# 11-DPLL-2.net
KiCad netlist of a schematic drawn in Altium Designer
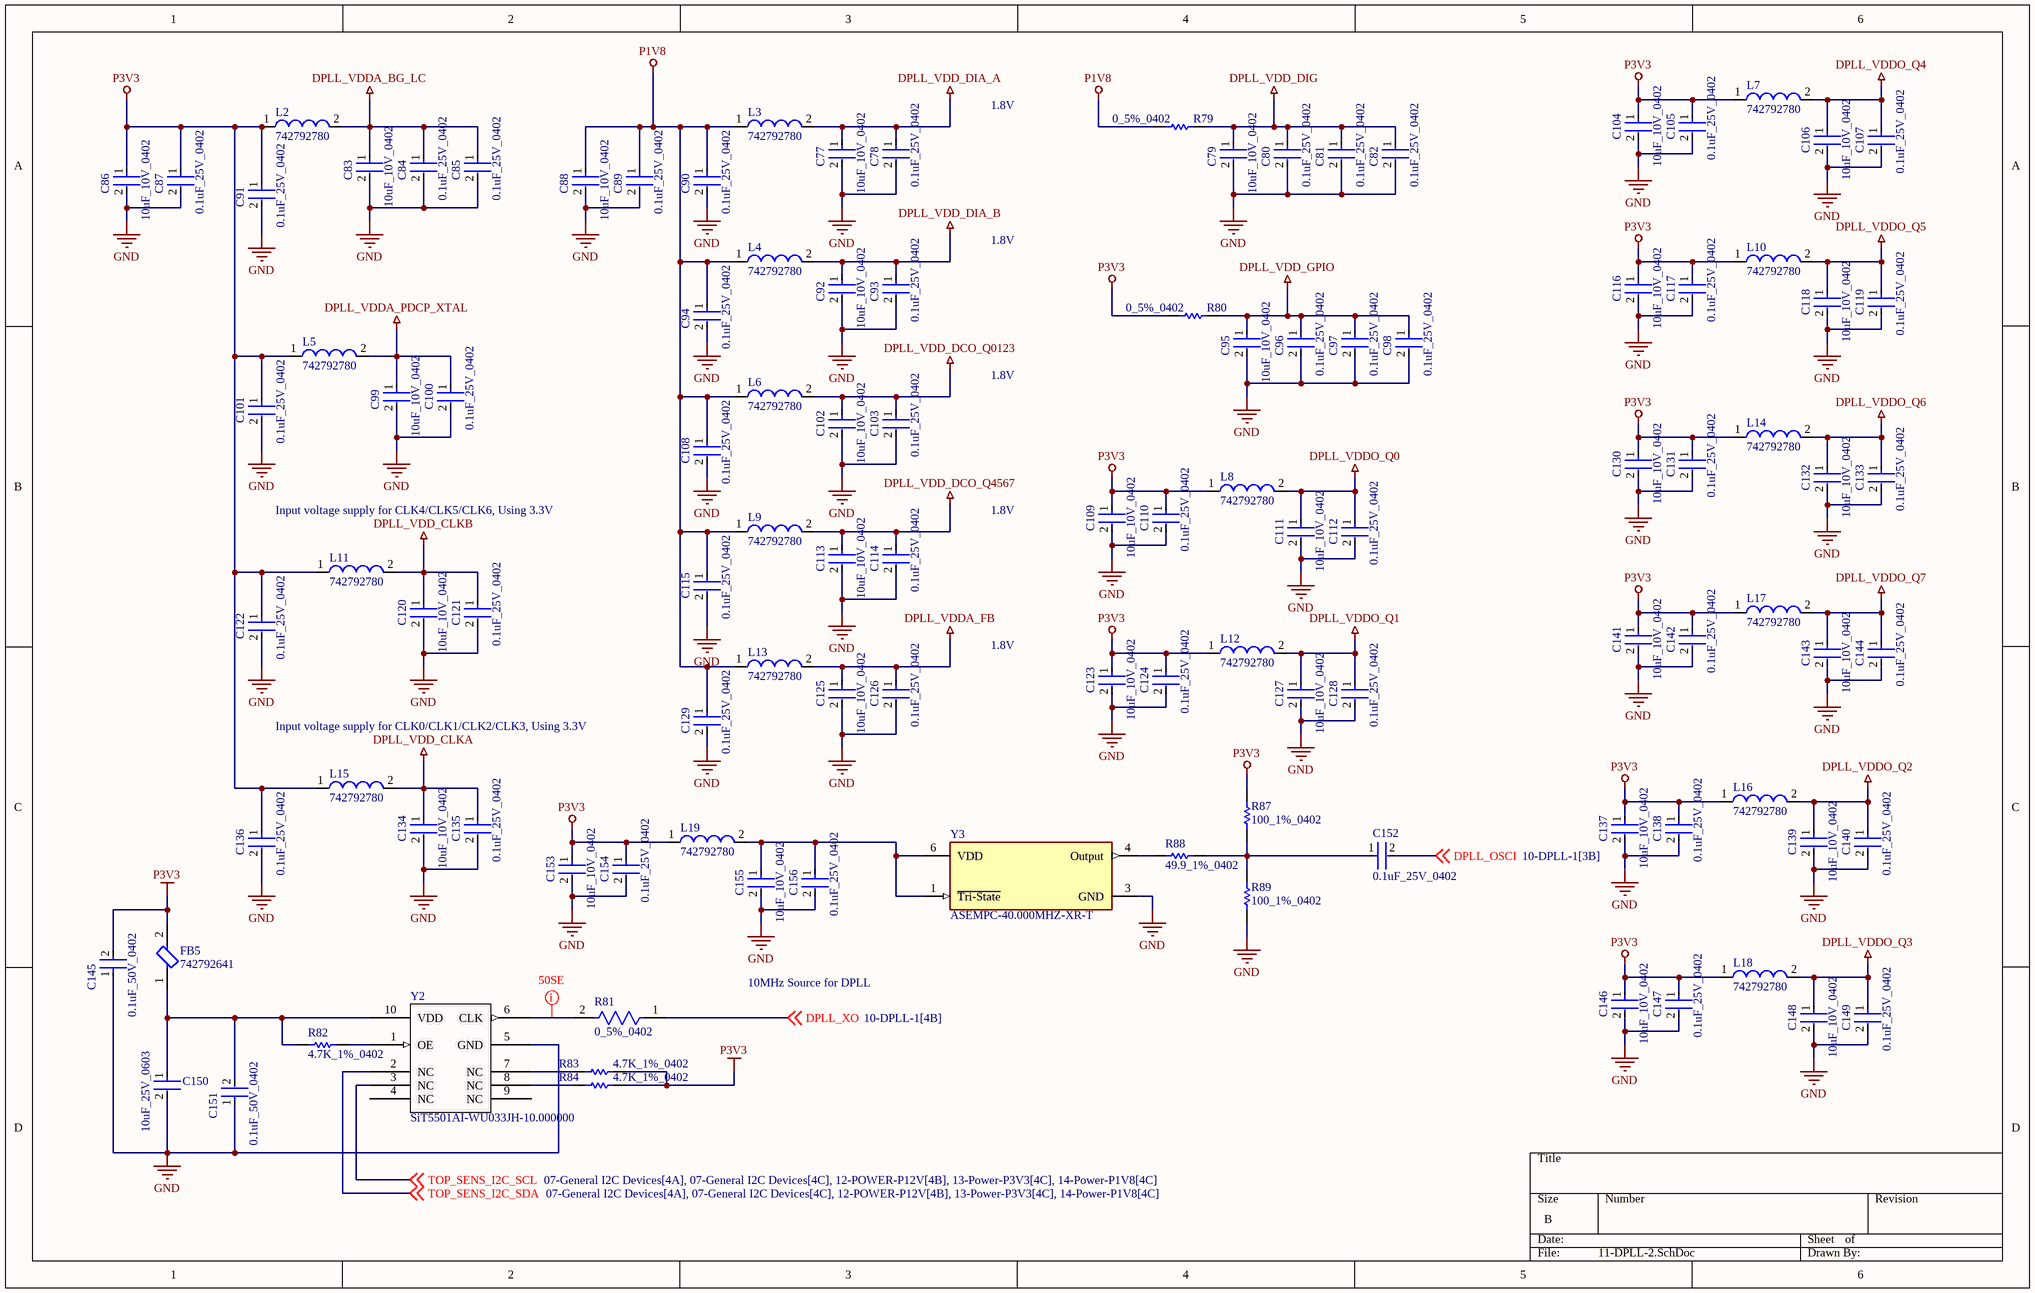
[diagram p0: 11-DPLL-2.SchDoc]

(export (version "E")
  (design (tool "Eeschema 10.0.6"))
  (components
    (comp (ref "C77")
      (value "10uF_10V_0402")
      (footprint "FP-CL05A106MP5NUNC-MFG")
      (description "CAP CER 10UF 10V X5R 0402")
      (fields
        (field (name "OCTOPART") "https://octopart.com/cl05a106mp5nunc-samsung-22457395")
        (field (name "TOLERANCE") "20%")
      )
      (libsource (lib "Altium Content Vault") (part "b4654b650e69147ec39a6b967a45e02"))
    )
    (comp (ref "C78")
      (value "0.1uF_25V_0402")
      (footprint "FP-0402-L_1_0_1-W_0_5_0_1-IPC_C")
      (description "General Purpose Ceramic Capacitor, 0402, 100nF, 10%, X7R, 15%, 25V")
      (fields (field (name "VOLTAGE") "25V") (field (name "TOLERANCE") "10%"))
      (libsource (lib "Altium Content Vault") (part "b4654b650e69147ec39a6b967a45e02"))
    )
    (comp (ref "C79")
      (value "10uF_10V_0402")
      (footprint "FP-CL05A106MP5NUNC-MFG")
      (description "CAP CER 10UF 10V X5R 0402")
      (fields
        (field (name "OCTOPART") "https://octopart.com/cl05a106mp5nunc-samsung-22457395")
        (field (name "TOLERANCE") "20%")
      )
      (libsource (lib "Altium Content Vault") (part "b4654b650e69147ec39a6b967a45e02"))
    )
    (comp (ref "C80")
      (value "0.1uF_25V_0402")
      (footprint "FP-0402-L_1_0_1-W_0_5_0_1-IPC_C")
      (description "General Purpose Ceramic Capacitor, 0402, 100nF, 10%, X7R, 15%, 25V")
      (fields (field (name "VOLTAGE") "25V") (field (name "TOLERANCE") "10%"))
      (libsource (lib "Altium Content Vault") (part "b4654b650e69147ec39a6b967a45e02"))
    )
    (comp (ref "C81")
      (value "0.1uF_25V_0402")
      (footprint "FP-0402-L_1_0_1-W_0_5_0_1-IPC_C")
      (description "General Purpose Ceramic Capacitor, 0402, 100nF, 10%, X7R, 15%, 25V")
      (fields (field (name "VOLTAGE") "25V") (field (name "TOLERANCE") "10%"))
      (libsource (lib "Altium Content Vault") (part "b4654b650e69147ec39a6b967a45e02"))
    )
    (comp (ref "C82")
      (value "0.1uF_25V_0402")
      (footprint "FP-0402-L_1_0_1-W_0_5_0_1-IPC_C")
      (description "General Purpose Ceramic Capacitor, 0402, 100nF, 10%, X7R, 15%, 25V")
      (fields (field (name "VOLTAGE") "25V") (field (name "TOLERANCE") "10%"))
      (libsource (lib "Altium Content Vault") (part "b4654b650e69147ec39a6b967a45e02"))
    )
    (comp (ref "C83")
      (value "10uF_10V_0402")
      (footprint "FP-CL05A106MP5NUNC-MFG")
      (description "CAP CER 10UF 10V X5R 0402")
      (fields
        (field (name "OCTOPART") "https://octopart.com/cl05a106mp5nunc-samsung-22457395")
        (field (name "TOLERANCE") "20%")
      )
      (libsource (lib "Altium Content Vault") (part "b4654b650e69147ec39a6b967a45e02"))
    )
    (comp (ref "C84")
      (value "0.1uF_25V_0402")
      (footprint "FP-0402-L_1_0_1-W_0_5_0_1-IPC_C")
      (description "General Purpose Ceramic Capacitor, 0402, 100nF, 10%, X7R, 15%, 25V")
      (fields (field (name "VOLTAGE") "25V") (field (name "TOLERANCE") "10%"))
      (libsource (lib "Altium Content Vault") (part "b4654b650e69147ec39a6b967a45e02"))
    )
    (comp (ref "C85")
      (value "0.1uF_25V_0402")
      (footprint "FP-0402-L_1_0_1-W_0_5_0_1-IPC_C")
      (description "General Purpose Ceramic Capacitor, 0402, 100nF, 10%, X7R, 15%, 25V")
      (fields (field (name "VOLTAGE") "25V") (field (name "TOLERANCE") "10%"))
      (libsource (lib "Altium Content Vault") (part "b4654b650e69147ec39a6b967a45e02"))
    )
    (comp (ref "C86")
      (value "10uF_10V_0402")
      (footprint "FP-CL05A106MP5NUNC-MFG")
      (description "CAP CER 10UF 10V X5R 0402")
      (fields
        (field (name "OCTOPART") "https://octopart.com/cl05a106mp5nunc-samsung-22457395")
        (field (name "TOLERANCE") "20%")
      )
      (libsource (lib "Altium Content Vault") (part "b4654b650e69147ec39a6b967a45e02"))
    )
    (comp (ref "C87")
      (value "0.1uF_25V_0402")
      (footprint "FP-0402-L_1_0_1-W_0_5_0_1-IPC_C")
      (description "General Purpose Ceramic Capacitor, 0402, 100nF, 10%, X7R, 15%, 25V")
      (fields (field (name "VOLTAGE") "25V") (field (name "TOLERANCE") "10%"))
      (libsource (lib "Altium Content Vault") (part "b4654b650e69147ec39a6b967a45e02"))
    )
    (comp (ref "C88")
      (value "10uF_10V_0402")
      (footprint "FP-CL05A106MP5NUNC-MFG")
      (description "CAP CER 10UF 10V X5R 0402")
      (fields
        (field (name "OCTOPART") "https://octopart.com/cl05a106mp5nunc-samsung-22457395")
        (field (name "TOLERANCE") "20%")
      )
      (libsource (lib "Altium Content Vault") (part "b4654b650e69147ec39a6b967a45e02"))
    )
    (comp (ref "C89")
      (value "0.1uF_25V_0402")
      (footprint "FP-0402-L_1_0_1-W_0_5_0_1-IPC_C")
      (description "General Purpose Ceramic Capacitor, 0402, 100nF, 10%, X7R, 15%, 25V")
      (fields (field (name "VOLTAGE") "25V") (field (name "TOLERANCE") "10%"))
      (libsource (lib "Altium Content Vault") (part "b4654b650e69147ec39a6b967a45e02"))
    )
    (comp (ref "C90")
      (value "0.1uF_25V_0402")
      (footprint "FP-0402-L_1_0_1-W_0_5_0_1-IPC_C")
      (description "General Purpose Ceramic Capacitor, 0402, 100nF, 10%, X7R, 15%, 25V")
      (fields (field (name "VOLTAGE") "25V") (field (name "TOLERANCE") "10%"))
      (libsource (lib "Altium Content Vault") (part "b4654b650e69147ec39a6b967a45e02"))
    )
    (comp (ref "C91")
      (value "0.1uF_25V_0402")
      (footprint "FP-0402-L_1_0_1-W_0_5_0_1-IPC_C")
      (description "General Purpose Ceramic Capacitor, 0402, 100nF, 10%, X7R, 15%, 25V")
      (fields (field (name "VOLTAGE") "25V") (field (name "TOLERANCE") "10%"))
      (libsource (lib "Altium Content Vault") (part "b4654b650e69147ec39a6b967a45e02"))
    )
    (comp (ref "C92")
      (value "10uF_10V_0402")
      (footprint "FP-CL05A106MP5NUNC-MFG")
      (description "CAP CER 10UF 10V X5R 0402")
      (fields
        (field (name "OCTOPART") "https://octopart.com/cl05a106mp5nunc-samsung-22457395")
        (field (name "TOLERANCE") "20%")
      )
      (libsource (lib "Altium Content Vault") (part "b4654b650e69147ec39a6b967a45e02"))
    )
    (comp (ref "C93")
      (value "0.1uF_25V_0402")
      (footprint "FP-0402-L_1_0_1-W_0_5_0_1-IPC_C")
      (description "General Purpose Ceramic Capacitor, 0402, 100nF, 10%, X7R, 15%, 25V")
      (fields (field (name "VOLTAGE") "25V") (field (name "TOLERANCE") "10%"))
      (libsource (lib "Altium Content Vault") (part "b4654b650e69147ec39a6b967a45e02"))
    )
    (comp (ref "C94")
      (value "0.1uF_25V_0402")
      (footprint "FP-0402-L_1_0_1-W_0_5_0_1-IPC_C")
      (description "General Purpose Ceramic Capacitor, 0402, 100nF, 10%, X7R, 15%, 25V")
      (fields (field (name "VOLTAGE") "25V") (field (name "TOLERANCE") "10%"))
      (libsource (lib "Altium Content Vault") (part "b4654b650e69147ec39a6b967a45e02"))
    )
    (comp (ref "C95")
      (value "10uF_10V_0402")
      (footprint "FP-CL05A106MP5NUNC-MFG")
      (description "CAP CER 10UF 10V X5R 0402")
      (fields
        (field (name "OCTOPART") "https://octopart.com/cl05a106mp5nunc-samsung-22457395")
        (field (name "TOLERANCE") "20%")
      )
      (libsource (lib "Altium Content Vault") (part "b4654b650e69147ec39a6b967a45e02"))
    )
    (comp (ref "C96")
      (value "0.1uF_25V_0402")
      (footprint "FP-0402-L_1_0_1-W_0_5_0_1-IPC_C")
      (description "General Purpose Ceramic Capacitor, 0402, 100nF, 10%, X7R, 15%, 25V")
      (fields (field (name "VOLTAGE") "25V") (field (name "TOLERANCE") "10%"))
      (libsource (lib "Altium Content Vault") (part "b4654b650e69147ec39a6b967a45e02"))
    )
    (comp (ref "C97")
      (value "0.1uF_25V_0402")
      (footprint "FP-0402-L_1_0_1-W_0_5_0_1-IPC_C")
      (description "General Purpose Ceramic Capacitor, 0402, 100nF, 10%, X7R, 15%, 25V")
      (fields (field (name "VOLTAGE") "25V") (field (name "TOLERANCE") "10%"))
      (libsource (lib "Altium Content Vault") (part "b4654b650e69147ec39a6b967a45e02"))
    )
    (comp (ref "C98")
      (value "0.1uF_25V_0402")
      (footprint "FP-0402-L_1_0_1-W_0_5_0_1-IPC_C")
      (description "General Purpose Ceramic Capacitor, 0402, 100nF, 10%, X7R, 15%, 25V")
      (fields (field (name "VOLTAGE") "25V") (field (name "TOLERANCE") "10%"))
      (libsource (lib "Altium Content Vault") (part "b4654b650e69147ec39a6b967a45e02"))
    )
    (comp (ref "C99")
      (value "10uF_10V_0402")
      (footprint "FP-CL05A106MP5NUNC-MFG")
      (description "CAP CER 10UF 10V X5R 0402")
      (fields
        (field (name "OCTOPART") "https://octopart.com/cl05a106mp5nunc-samsung-22457395")
        (field (name "TOLERANCE") "20%")
      )
      (libsource (lib "Altium Content Vault") (part "b4654b650e69147ec39a6b967a45e02"))
    )
    (comp (ref "C100")
      (value "0.1uF_25V_0402")
      (footprint "FP-0402-L_1_0_1-W_0_5_0_1-IPC_C")
      (description "General Purpose Ceramic Capacitor, 0402, 100nF, 10%, X7R, 15%, 25V")
      (fields (field (name "VOLTAGE") "25V") (field (name "TOLERANCE") "10%"))
      (libsource (lib "Altium Content Vault") (part "b4654b650e69147ec39a6b967a45e02"))
    )
    (comp (ref "C101")
      (value "0.1uF_25V_0402")
      (footprint "FP-0402-L_1_0_1-W_0_5_0_1-IPC_C")
      (description "General Purpose Ceramic Capacitor, 0402, 100nF, 10%, X7R, 15%, 25V")
      (fields (field (name "VOLTAGE") "25V") (field (name "TOLERANCE") "10%"))
      (libsource (lib "Altium Content Vault") (part "b4654b650e69147ec39a6b967a45e02"))
    )
    (comp (ref "C102")
      (value "10uF_10V_0402")
      (footprint "FP-CL05A106MP5NUNC-MFG")
      (description "CAP CER 10UF 10V X5R 0402")
      (fields
        (field (name "OCTOPART") "https://octopart.com/cl05a106mp5nunc-samsung-22457395")
        (field (name "TOLERANCE") "20%")
      )
      (libsource (lib "Altium Content Vault") (part "b4654b650e69147ec39a6b967a45e02"))
    )
    (comp (ref "C103")
      (value "0.1uF_25V_0402")
      (footprint "FP-0402-L_1_0_1-W_0_5_0_1-IPC_C")
      (description "General Purpose Ceramic Capacitor, 0402, 100nF, 10%, X7R, 15%, 25V")
      (fields (field (name "VOLTAGE") "25V") (field (name "TOLERANCE") "10%"))
      (libsource (lib "Altium Content Vault") (part "b4654b650e69147ec39a6b967a45e02"))
    )
    (comp (ref "C104")
      (value "10uF_10V_0402")
      (footprint "FP-CL05A106MP5NUNC-MFG")
      (description "CAP CER 10UF 10V X5R 0402")
      (fields
        (field (name "OCTOPART") "https://octopart.com/cl05a106mp5nunc-samsung-22457395")
        (field (name "TOLERANCE") "20%")
      )
      (libsource (lib "Altium Content Vault") (part "b4654b650e69147ec39a6b967a45e02"))
    )
    (comp (ref "C105")
      (value "0.1uF_25V_0402")
      (footprint "FP-0402-L_1_0_1-W_0_5_0_1-IPC_C")
      (description "General Purpose Ceramic Capacitor, 0402, 100nF, 10%, X7R, 15%, 25V")
      (fields (field (name "VOLTAGE") "25V") (field (name "TOLERANCE") "10%"))
      (libsource (lib "Altium Content Vault") (part "b4654b650e69147ec39a6b967a45e02"))
    )
    (comp (ref "C106")
      (value "10uF_10V_0402")
      (footprint "FP-CL05A106MP5NUNC-MFG")
      (description "CAP CER 10UF 10V X5R 0402")
      (fields
        (field (name "OCTOPART") "https://octopart.com/cl05a106mp5nunc-samsung-22457395")
        (field (name "TOLERANCE") "20%")
      )
      (libsource (lib "Altium Content Vault") (part "b4654b650e69147ec39a6b967a45e02"))
    )
    (comp (ref "C107")
      (value "0.1uF_25V_0402")
      (footprint "FP-0402-L_1_0_1-W_0_5_0_1-IPC_C")
      (description "General Purpose Ceramic Capacitor, 0402, 100nF, 10%, X7R, 15%, 25V")
      (fields (field (name "VOLTAGE") "25V") (field (name "TOLERANCE") "10%"))
      (libsource (lib "Altium Content Vault") (part "b4654b650e69147ec39a6b967a45e02"))
    )
    (comp (ref "C108")
      (value "0.1uF_25V_0402")
      (footprint "FP-0402-L_1_0_1-W_0_5_0_1-IPC_C")
      (description "General Purpose Ceramic Capacitor, 0402, 100nF, 10%, X7R, 15%, 25V")
      (fields (field (name "VOLTAGE") "25V") (field (name "TOLERANCE") "10%"))
      (libsource (lib "Altium Content Vault") (part "b4654b650e69147ec39a6b967a45e02"))
    )
    (comp (ref "C109")
      (value "10uF_10V_0402")
      (footprint "FP-CL05A106MP5NUNC-MFG")
      (description "CAP CER 10UF 10V X5R 0402")
      (fields
        (field (name "OCTOPART") "https://octopart.com/cl05a106mp5nunc-samsung-22457395")
        (field (name "TOLERANCE") "20%")
      )
      (libsource (lib "Altium Content Vault") (part "b4654b650e69147ec39a6b967a45e02"))
    )
    (comp (ref "C110")
      (value "0.1uF_25V_0402")
      (footprint "FP-0402-L_1_0_1-W_0_5_0_1-IPC_C")
      (description "General Purpose Ceramic Capacitor, 0402, 100nF, 10%, X7R, 15%, 25V")
      (fields (field (name "VOLTAGE") "25V") (field (name "TOLERANCE") "10%"))
      (libsource (lib "Altium Content Vault") (part "b4654b650e69147ec39a6b967a45e02"))
    )
    (comp (ref "C111")
      (value "10uF_10V_0402")
      (footprint "FP-CL05A106MP5NUNC-MFG")
      (description "CAP CER 10UF 10V X5R 0402")
      (fields
        (field (name "OCTOPART") "https://octopart.com/cl05a106mp5nunc-samsung-22457395")
        (field (name "TOLERANCE") "20%")
      )
      (libsource (lib "Altium Content Vault") (part "b4654b650e69147ec39a6b967a45e02"))
    )
    (comp (ref "C112")
      (value "0.1uF_25V_0402")
      (footprint "FP-0402-L_1_0_1-W_0_5_0_1-IPC_C")
      (description "General Purpose Ceramic Capacitor, 0402, 100nF, 10%, X7R, 15%, 25V")
      (fields (field (name "VOLTAGE") "25V") (field (name "TOLERANCE") "10%"))
      (libsource (lib "Altium Content Vault") (part "b4654b650e69147ec39a6b967a45e02"))
    )
    (comp (ref "C113")
      (value "10uF_10V_0402")
      (footprint "FP-CL05A106MP5NUNC-MFG")
      (description "CAP CER 10UF 10V X5R 0402")
      (fields
        (field (name "OCTOPART") "https://octopart.com/cl05a106mp5nunc-samsung-22457395")
        (field (name "TOLERANCE") "20%")
      )
      (libsource (lib "Altium Content Vault") (part "b4654b650e69147ec39a6b967a45e02"))
    )
    (comp (ref "C114")
      (value "0.1uF_25V_0402")
      (footprint "FP-0402-L_1_0_1-W_0_5_0_1-IPC_C")
      (description "General Purpose Ceramic Capacitor, 0402, 100nF, 10%, X7R, 15%, 25V")
      (fields (field (name "VOLTAGE") "25V") (field (name "TOLERANCE") "10%"))
      (libsource (lib "Altium Content Vault") (part "b4654b650e69147ec39a6b967a45e02"))
    )
    (comp (ref "C115")
      (value "0.1uF_25V_0402")
      (footprint "FP-0402-L_1_0_1-W_0_5_0_1-IPC_C")
      (description "General Purpose Ceramic Capacitor, 0402, 100nF, 10%, X7R, 15%, 25V")
      (fields (field (name "VOLTAGE") "25V") (field (name "TOLERANCE") "10%"))
      (libsource (lib "Altium Content Vault") (part "b4654b650e69147ec39a6b967a45e02"))
    )
    (comp (ref "C116")
      (value "10uF_10V_0402")
      (footprint "FP-CL05A106MP5NUNC-MFG")
      (description "CAP CER 10UF 10V X5R 0402")
      (fields
        (field (name "OCTOPART") "https://octopart.com/cl05a106mp5nunc-samsung-22457395")
        (field (name "TOLERANCE") "20%")
      )
      (libsource (lib "Altium Content Vault") (part "b4654b650e69147ec39a6b967a45e02"))
    )
    (comp (ref "C117")
      (value "0.1uF_25V_0402")
      (footprint "FP-0402-L_1_0_1-W_0_5_0_1-IPC_C")
      (description "General Purpose Ceramic Capacitor, 0402, 100nF, 10%, X7R, 15%, 25V")
      (fields (field (name "VOLTAGE") "25V") (field (name "TOLERANCE") "10%"))
      (libsource (lib "Altium Content Vault") (part "b4654b650e69147ec39a6b967a45e02"))
    )
    (comp (ref "C118")
      (value "10uF_10V_0402")
      (footprint "FP-CL05A106MP5NUNC-MFG")
      (description "CAP CER 10UF 10V X5R 0402")
      (fields
        (field (name "OCTOPART") "https://octopart.com/cl05a106mp5nunc-samsung-22457395")
        (field (name "TOLERANCE") "20%")
      )
      (libsource (lib "Altium Content Vault") (part "b4654b650e69147ec39a6b967a45e02"))
    )
    (comp (ref "C119")
      (value "0.1uF_25V_0402")
      (footprint "FP-0402-L_1_0_1-W_0_5_0_1-IPC_C")
      (description "General Purpose Ceramic Capacitor, 0402, 100nF, 10%, X7R, 15%, 25V")
      (fields (field (name "VOLTAGE") "25V") (field (name "TOLERANCE") "10%"))
      (libsource (lib "Altium Content Vault") (part "b4654b650e69147ec39a6b967a45e02"))
    )
    (comp (ref "C120")
      (value "10uF_10V_0402")
      (footprint "FP-CL05A106MP5NUNC-MFG")
      (description "CAP CER 10UF 10V X5R 0402")
      (fields
        (field (name "OCTOPART") "https://octopart.com/cl05a106mp5nunc-samsung-22457395")
        (field (name "TOLERANCE") "20%")
      )
      (libsource (lib "Altium Content Vault") (part "b4654b650e69147ec39a6b967a45e02"))
    )
    (comp (ref "C121")
      (value "0.1uF_25V_0402")
      (footprint "FP-0402-L_1_0_1-W_0_5_0_1-IPC_C")
      (description "General Purpose Ceramic Capacitor, 0402, 100nF, 10%, X7R, 15%, 25V")
      (fields (field (name "VOLTAGE") "25V") (field (name "TOLERANCE") "10%"))
      (libsource (lib "Altium Content Vault") (part "b4654b650e69147ec39a6b967a45e02"))
    )
    (comp (ref "C122")
      (value "0.1uF_25V_0402")
      (footprint "FP-0402-L_1_0_1-W_0_5_0_1-IPC_C")
      (description "General Purpose Ceramic Capacitor, 0402, 100nF, 10%, X7R, 15%, 25V")
      (fields (field (name "VOLTAGE") "25V") (field (name "TOLERANCE") "10%"))
      (libsource (lib "Altium Content Vault") (part "b4654b650e69147ec39a6b967a45e02"))
    )
    (comp (ref "C123")
      (value "10uF_10V_0402")
      (footprint "FP-CL05A106MP5NUNC-MFG")
      (description "CAP CER 10UF 10V X5R 0402")
      (fields
        (field (name "OCTOPART") "https://octopart.com/cl05a106mp5nunc-samsung-22457395")
        (field (name "TOLERANCE") "20%")
      )
      (libsource (lib "Altium Content Vault") (part "b4654b650e69147ec39a6b967a45e02"))
    )
    (comp (ref "C124")
      (value "0.1uF_25V_0402")
      (footprint "FP-0402-L_1_0_1-W_0_5_0_1-IPC_C")
      (description "General Purpose Ceramic Capacitor, 0402, 100nF, 10%, X7R, 15%, 25V")
      (fields (field (name "VOLTAGE") "25V") (field (name "TOLERANCE") "10%"))
      (libsource (lib "Altium Content Vault") (part "b4654b650e69147ec39a6b967a45e02"))
    )
    (comp (ref "C125")
      (value "10uF_10V_0402")
      (footprint "FP-CL05A106MP5NUNC-MFG")
      (description "CAP CER 10UF 10V X5R 0402")
      (fields
        (field (name "OCTOPART") "https://octopart.com/cl05a106mp5nunc-samsung-22457395")
        (field (name "TOLERANCE") "20%")
      )
      (libsource (lib "Altium Content Vault") (part "b4654b650e69147ec39a6b967a45e02"))
    )
    (comp (ref "C126")
      (value "0.1uF_25V_0402")
      (footprint "FP-0402-L_1_0_1-W_0_5_0_1-IPC_C")
      (description "General Purpose Ceramic Capacitor, 0402, 100nF, 10%, X7R, 15%, 25V")
      (fields (field (name "VOLTAGE") "25V") (field (name "TOLERANCE") "10%"))
      (libsource (lib "Altium Content Vault") (part "b4654b650e69147ec39a6b967a45e02"))
    )
    (comp (ref "C127")
      (value "10uF_10V_0402")
      (footprint "FP-CL05A106MP5NUNC-MFG")
      (description "CAP CER 10UF 10V X5R 0402")
      (fields
        (field (name "OCTOPART") "https://octopart.com/cl05a106mp5nunc-samsung-22457395")
        (field (name "TOLERANCE") "20%")
      )
      (libsource (lib "Altium Content Vault") (part "b4654b650e69147ec39a6b967a45e02"))
    )
    (comp (ref "C128")
      (value "0.1uF_25V_0402")
      (footprint "FP-0402-L_1_0_1-W_0_5_0_1-IPC_C")
      (description "General Purpose Ceramic Capacitor, 0402, 100nF, 10%, X7R, 15%, 25V")
      (fields (field (name "VOLTAGE") "25V") (field (name "TOLERANCE") "10%"))
      (libsource (lib "Altium Content Vault") (part "b4654b650e69147ec39a6b967a45e02"))
    )
    (comp (ref "C129")
      (value "0.1uF_25V_0402")
      (footprint "FP-0402-L_1_0_1-W_0_5_0_1-IPC_C")
      (description "General Purpose Ceramic Capacitor, 0402, 100nF, 10%, X7R, 15%, 25V")
      (fields (field (name "VOLTAGE") "25V") (field (name "TOLERANCE") "10%"))
      (libsource (lib "Altium Content Vault") (part "b4654b650e69147ec39a6b967a45e02"))
    )
    (comp (ref "C130")
      (value "10uF_10V_0402")
      (footprint "FP-CL05A106MP5NUNC-MFG")
      (description "CAP CER 10UF 10V X5R 0402")
      (fields
        (field (name "OCTOPART") "https://octopart.com/cl05a106mp5nunc-samsung-22457395")
        (field (name "TOLERANCE") "20%")
      )
      (libsource (lib "Altium Content Vault") (part "b4654b650e69147ec39a6b967a45e02"))
    )
    (comp (ref "C131")
      (value "0.1uF_25V_0402")
      (footprint "FP-0402-L_1_0_1-W_0_5_0_1-IPC_C")
      (description "General Purpose Ceramic Capacitor, 0402, 100nF, 10%, X7R, 15%, 25V")
      (fields (field (name "VOLTAGE") "25V") (field (name "TOLERANCE") "10%"))
      (libsource (lib "Altium Content Vault") (part "b4654b650e69147ec39a6b967a45e02"))
    )
    (comp (ref "C132")
      (value "10uF_10V_0402")
      (footprint "FP-CL05A106MP5NUNC-MFG")
      (description "CAP CER 10UF 10V X5R 0402")
      (fields
        (field (name "OCTOPART") "https://octopart.com/cl05a106mp5nunc-samsung-22457395")
        (field (name "TOLERANCE") "20%")
      )
      (libsource (lib "Altium Content Vault") (part "b4654b650e69147ec39a6b967a45e02"))
    )
    (comp (ref "C133")
      (value "0.1uF_25V_0402")
      (footprint "FP-0402-L_1_0_1-W_0_5_0_1-IPC_C")
      (description "General Purpose Ceramic Capacitor, 0402, 100nF, 10%, X7R, 15%, 25V")
      (fields (field (name "VOLTAGE") "25V") (field (name "TOLERANCE") "10%"))
      (libsource (lib "Altium Content Vault") (part "b4654b650e69147ec39a6b967a45e02"))
    )
    (comp (ref "C134")
      (value "10uF_10V_0402")
      (footprint "FP-CL05A106MP5NUNC-MFG")
      (description "CAP CER 10UF 10V X5R 0402")
      (fields
        (field (name "OCTOPART") "https://octopart.com/cl05a106mp5nunc-samsung-22457395")
        (field (name "TOLERANCE") "20%")
      )
      (libsource (lib "Altium Content Vault") (part "b4654b650e69147ec39a6b967a45e02"))
    )
    (comp (ref "C135")
      (value "0.1uF_25V_0402")
      (footprint "FP-0402-L_1_0_1-W_0_5_0_1-IPC_C")
      (description "General Purpose Ceramic Capacitor, 0402, 100nF, 10%, X7R, 15%, 25V")
      (fields (field (name "VOLTAGE") "25V") (field (name "TOLERANCE") "10%"))
      (libsource (lib "Altium Content Vault") (part "b4654b650e69147ec39a6b967a45e02"))
    )
    (comp (ref "C136")
      (value "0.1uF_25V_0402")
      (footprint "FP-0402-L_1_0_1-W_0_5_0_1-IPC_C")
      (description "General Purpose Ceramic Capacitor, 0402, 100nF, 10%, X7R, 15%, 25V")
      (fields (field (name "VOLTAGE") "25V") (field (name "TOLERANCE") "10%"))
      (libsource (lib "Altium Content Vault") (part "b4654b650e69147ec39a6b967a45e02"))
    )
    (comp (ref "C137")
      (value "10uF_10V_0402")
      (footprint "FP-CL05A106MP5NUNC-MFG")
      (description "CAP CER 10UF 10V X5R 0402")
      (fields
        (field (name "OCTOPART") "https://octopart.com/cl05a106mp5nunc-samsung-22457395")
        (field (name "TOLERANCE") "20%")
      )
      (libsource (lib "Altium Content Vault") (part "b4654b650e69147ec39a6b967a45e02"))
    )
    (comp (ref "C138")
      (value "0.1uF_25V_0402")
      (footprint "FP-0402-L_1_0_1-W_0_5_0_1-IPC_C")
      (description "General Purpose Ceramic Capacitor, 0402, 100nF, 10%, X7R, 15%, 25V")
      (fields (field (name "VOLTAGE") "25V") (field (name "TOLERANCE") "10%"))
      (libsource (lib "Altium Content Vault") (part "b4654b650e69147ec39a6b967a45e02"))
    )
    (comp (ref "C139")
      (value "10uF_10V_0402")
      (footprint "FP-CL05A106MP5NUNC-MFG")
      (description "CAP CER 10UF 10V X5R 0402")
      (fields
        (field (name "OCTOPART") "https://octopart.com/cl05a106mp5nunc-samsung-22457395")
        (field (name "TOLERANCE") "20%")
      )
      (libsource (lib "Altium Content Vault") (part "b4654b650e69147ec39a6b967a45e02"))
    )
    (comp (ref "C140")
      (value "0.1uF_25V_0402")
      (footprint "FP-0402-L_1_0_1-W_0_5_0_1-IPC_C")
      (description "General Purpose Ceramic Capacitor, 0402, 100nF, 10%, X7R, 15%, 25V")
      (fields (field (name "VOLTAGE") "25V") (field (name "TOLERANCE") "10%"))
      (libsource (lib "Altium Content Vault") (part "b4654b650e69147ec39a6b967a45e02"))
    )
    (comp (ref "C141")
      (value "10uF_10V_0402")
      (footprint "FP-CL05A106MP5NUNC-MFG")
      (description "CAP CER 10UF 10V X5R 0402")
      (fields
        (field (name "OCTOPART") "https://octopart.com/cl05a106mp5nunc-samsung-22457395")
        (field (name "TOLERANCE") "20%")
      )
      (libsource (lib "Altium Content Vault") (part "b4654b650e69147ec39a6b967a45e02"))
    )
    (comp (ref "C142")
      (value "0.1uF_25V_0402")
      (footprint "FP-0402-L_1_0_1-W_0_5_0_1-IPC_C")
      (description "General Purpose Ceramic Capacitor, 0402, 100nF, 10%, X7R, 15%, 25V")
      (fields (field (name "VOLTAGE") "25V") (field (name "TOLERANCE") "10%"))
      (libsource (lib "Altium Content Vault") (part "b4654b650e69147ec39a6b967a45e02"))
    )
    (comp (ref "C143")
      (value "10uF_10V_0402")
      (footprint "FP-CL05A106MP5NUNC-MFG")
      (description "CAP CER 10UF 10V X5R 0402")
      (fields
        (field (name "OCTOPART") "https://octopart.com/cl05a106mp5nunc-samsung-22457395")
        (field (name "TOLERANCE") "20%")
      )
      (libsource (lib "Altium Content Vault") (part "b4654b650e69147ec39a6b967a45e02"))
    )
    (comp (ref "C144")
      (value "0.1uF_25V_0402")
      (footprint "FP-0402-L_1_0_1-W_0_5_0_1-IPC_C")
      (description "General Purpose Ceramic Capacitor, 0402, 100nF, 10%, X7R, 15%, 25V")
      (fields (field (name "VOLTAGE") "25V") (field (name "TOLERANCE") "10%"))
      (libsource (lib "Altium Content Vault") (part "b4654b650e69147ec39a6b967a45e02"))
    )
    (comp (ref "C145")
      (value "0.1uF_50V_0402")
      (footprint "FP-C1005-050-0_05-IPC_C")
      (description "Multilayer Ceramic Capacitors 100nF ±10% 50V X7R SMD 0402")
      (fields (field (name "VOLTAGE") "50V") (field (name "TOLERANCE") "10%"))
      (libsource (lib "Altium Content Vault") (part "b4654b650e69147ec39a6b967a45e02"))
    )
    (comp (ref "C146")
      (value "10uF_10V_0402")
      (footprint "FP-CL05A106MP5NUNC-MFG")
      (description "CAP CER 10UF 10V X5R 0402")
      (fields
        (field (name "OCTOPART") "https://octopart.com/cl05a106mp5nunc-samsung-22457395")
        (field (name "TOLERANCE") "20%")
      )
      (libsource (lib "Altium Content Vault") (part "b4654b650e69147ec39a6b967a45e02"))
    )
    (comp (ref "C147")
      (value "0.1uF_25V_0402")
      (footprint "FP-0402-L_1_0_1-W_0_5_0_1-IPC_C")
      (description "General Purpose Ceramic Capacitor, 0402, 100nF, 10%, X7R, 15%, 25V")
      (fields (field (name "VOLTAGE") "25V") (field (name "TOLERANCE") "10%"))
      (libsource (lib "Altium Content Vault") (part "b4654b650e69147ec39a6b967a45e02"))
    )
    (comp (ref "C148")
      (value "10uF_10V_0402")
      (footprint "FP-CL05A106MP5NUNC-MFG")
      (description "CAP CER 10UF 10V X5R 0402")
      (fields
        (field (name "OCTOPART") "https://octopart.com/cl05a106mp5nunc-samsung-22457395")
        (field (name "TOLERANCE") "20%")
      )
      (libsource (lib "Altium Content Vault") (part "b4654b650e69147ec39a6b967a45e02"))
    )
    (comp (ref "C149")
      (value "0.1uF_25V_0402")
      (footprint "FP-0402-L_1_0_1-W_0_5_0_1-IPC_C")
      (description "General Purpose Ceramic Capacitor, 0402, 100nF, 10%, X7R, 15%, 25V")
      (fields (field (name "VOLTAGE") "25V") (field (name "TOLERANCE") "10%"))
      (libsource (lib "Altium Content Vault") (part "b4654b650e69147ec39a6b967a45e02"))
    )
    (comp (ref "C150")
      (value "10uF_25V_0603")
      (footprint "FP-CL10-IPC_C")
      (description "Cap Ceramic 10uF 25V X5R ±20% Pad SMD 0603 +85°C T/R")
      (fields (field (name "TOLERANCE") "20%"))
      (libsource (lib "Altium Content Vault") (part "b4654b650e69147ec39a6b967a45e02"))
    )
    (comp (ref "C151")
      (value "0.1uF_50V_0402")
      (footprint "FP-C1005-050-0_05-IPC_C")
      (description "Multilayer Ceramic Capacitors 100nF ±10% 50V X7R SMD 0402")
      (fields (field (name "VOLTAGE") "50V") (field (name "TOLERANCE") "10%"))
      (libsource (lib "Altium Content Vault") (part "b4654b650e69147ec39a6b967a45e02"))
    )
    (comp (ref "C152")
      (value "0.1uF_25V_0402")
      (footprint "FP-0402-L_1_0_1-W_0_5_0_1-IPC_C")
      (description "General Purpose Ceramic Capacitor, 0402, 100nF, 10%, X7R, 15%, 25V")
      (fields (field (name "VOLTAGE") "25V") (field (name "TOLERANCE") "10%"))
      (libsource (lib "Altium Content Vault") (part "b4654b650e69147ec39a6b967a45e02"))
    )
    (comp (ref "C153")
      (value "10uF_10V_0402")
      (footprint "FP-CL05A106MP5NUNC-MFG")
      (description "CAP CER 10UF 10V X5R 0402")
      (fields
        (field (name "OCTOPART") "https://octopart.com/cl05a106mp5nunc-samsung-22457395")
        (field (name "TOLERANCE") "20%")
      )
      (libsource (lib "Altium Content Vault") (part "b4654b650e69147ec39a6b967a45e02"))
    )
    (comp (ref "C154")
      (value "0.1uF_25V_0402")
      (footprint "FP-0402-L_1_0_1-W_0_5_0_1-IPC_C")
      (description "General Purpose Ceramic Capacitor, 0402, 100nF, 10%, X7R, 15%, 25V")
      (fields (field (name "VOLTAGE") "25V") (field (name "TOLERANCE") "10%"))
      (libsource (lib "Altium Content Vault") (part "b4654b650e69147ec39a6b967a45e02"))
    )
    (comp (ref "C155")
      (value "10uF_10V_0402")
      (footprint "FP-CL05A106MP5NUNC-MFG")
      (description "CAP CER 10UF 10V X5R 0402")
      (fields
        (field (name "OCTOPART") "https://octopart.com/cl05a106mp5nunc-samsung-22457395")
        (field (name "TOLERANCE") "20%")
      )
      (libsource (lib "Altium Content Vault") (part "b4654b650e69147ec39a6b967a45e02"))
    )
    (comp (ref "C156")
      (value "0.1uF_25V_0402")
      (footprint "FP-0402-L_1_0_1-W_0_5_0_1-IPC_C")
      (description "General Purpose Ceramic Capacitor, 0402, 100nF, 10%, X7R, 15%, 25V")
      (fields (field (name "VOLTAGE") "25V") (field (name "TOLERANCE") "10%"))
      (libsource (lib "Altium Content Vault") (part "b4654b650e69147ec39a6b967a45e02"))
    )
    (comp (ref "FB5")
      (value "742792641")
      (footprint "FP-742792641-MFG")
      (description "FERRITE BEAD 300 OHM 0603 1LN")
      (fields (field (name "TOLERANCE") "25%"))
      (libsource (lib "Altium Content Vault") (part "5f30dd21d616792df468990f7003faa"))
    )
    (comp (ref "L2")
      (value "742792780")
      (footprint "SMD-0402")
      (description "SMD EMI Suppression Ferrite Bead WE-CBF, Z = 220 Ohm")
      (libsource (lib "Altium Content Vault") (part "PAS-IND-INDUCTOR-2"))
    )
    (comp (ref "L3")
      (value "742792780")
      (footprint "SMD-0402")
      (description "SMD EMI Suppression Ferrite Bead WE-CBF, Z = 220 Ohm")
      (libsource (lib "Altium Content Vault") (part "PAS-IND-INDUCTOR-2"))
    )
    (comp (ref "L4")
      (value "742792780")
      (footprint "SMD-0402")
      (description "SMD EMI Suppression Ferrite Bead WE-CBF, Z = 220 Ohm")
      (libsource (lib "Altium Content Vault") (part "PAS-IND-INDUCTOR-2"))
    )
    (comp (ref "L5")
      (value "742792780")
      (footprint "SMD-0402")
      (description "SMD EMI Suppression Ferrite Bead WE-CBF, Z = 220 Ohm")
      (libsource (lib "Altium Content Vault") (part "PAS-IND-INDUCTOR-2"))
    )
    (comp (ref "L6")
      (value "742792780")
      (footprint "SMD-0402")
      (description "SMD EMI Suppression Ferrite Bead WE-CBF, Z = 220 Ohm")
      (libsource (lib "Altium Content Vault") (part "PAS-IND-INDUCTOR-2"))
    )
    (comp (ref "L7")
      (value "742792780")
      (footprint "SMD-0402")
      (description "SMD EMI Suppression Ferrite Bead WE-CBF, Z = 220 Ohm")
      (libsource (lib "Altium Content Vault") (part "PAS-IND-INDUCTOR-2"))
    )
    (comp (ref "L8")
      (value "742792780")
      (footprint "SMD-0402")
      (description "SMD EMI Suppression Ferrite Bead WE-CBF, Z = 220 Ohm")
      (libsource (lib "Altium Content Vault") (part "PAS-IND-INDUCTOR-2"))
    )
    (comp (ref "L9")
      (value "742792780")
      (footprint "SMD-0402")
      (description "SMD EMI Suppression Ferrite Bead WE-CBF, Z = 220 Ohm")
      (libsource (lib "Altium Content Vault") (part "PAS-IND-INDUCTOR-2"))
    )
    (comp (ref "L10")
      (value "742792780")
      (footprint "SMD-0402")
      (description "SMD EMI Suppression Ferrite Bead WE-CBF, Z = 220 Ohm")
      (libsource (lib "Altium Content Vault") (part "PAS-IND-INDUCTOR-2"))
    )
    (comp (ref "L11")
      (value "742792780")
      (footprint "SMD-0402")
      (description "SMD EMI Suppression Ferrite Bead WE-CBF, Z = 220 Ohm")
      (libsource (lib "Altium Content Vault") (part "PAS-IND-INDUCTOR-2"))
    )
    (comp (ref "L12")
      (value "742792780")
      (footprint "SMD-0402")
      (description "SMD EMI Suppression Ferrite Bead WE-CBF, Z = 220 Ohm")
      (libsource (lib "Altium Content Vault") (part "PAS-IND-INDUCTOR-2"))
    )
    (comp (ref "L13")
      (value "742792780")
      (footprint "SMD-0402")
      (description "SMD EMI Suppression Ferrite Bead WE-CBF, Z = 220 Ohm")
      (libsource (lib "Altium Content Vault") (part "PAS-IND-INDUCTOR-2"))
    )
    (comp (ref "L14")
      (value "742792780")
      (footprint "SMD-0402")
      (description "SMD EMI Suppression Ferrite Bead WE-CBF, Z = 220 Ohm")
      (libsource (lib "Altium Content Vault") (part "PAS-IND-INDUCTOR-2"))
    )
    (comp (ref "L15")
      (value "742792780")
      (footprint "SMD-0402")
      (description "SMD EMI Suppression Ferrite Bead WE-CBF, Z = 220 Ohm")
      (libsource (lib "Altium Content Vault") (part "PAS-IND-INDUCTOR-2"))
    )
    (comp (ref "L16")
      (value "742792780")
      (footprint "SMD-0402")
      (description "SMD EMI Suppression Ferrite Bead WE-CBF, Z = 220 Ohm")
      (libsource (lib "Altium Content Vault") (part "PAS-IND-INDUCTOR-2"))
    )
    (comp (ref "L17")
      (value "742792780")
      (footprint "SMD-0402")
      (description "SMD EMI Suppression Ferrite Bead WE-CBF, Z = 220 Ohm")
      (libsource (lib "Altium Content Vault") (part "PAS-IND-INDUCTOR-2"))
    )
    (comp (ref "L18")
      (value "742792780")
      (footprint "SMD-0402")
      (description "SMD EMI Suppression Ferrite Bead WE-CBF, Z = 220 Ohm")
      (libsource (lib "Altium Content Vault") (part "PAS-IND-INDUCTOR-2"))
    )
    (comp (ref "L19")
      (value "742792780")
      (footprint "SMD-0402")
      (description "SMD EMI Suppression Ferrite Bead WE-CBF, Z = 220 Ohm")
      (libsource (lib "Altium Content Vault") (part "PAS-IND-INDUCTOR-2"))
    )
    (comp (ref "R79")
      (value "0_5%_0402")
      (footprint "RESC1005X40X25LL10T10")
      (fields (field (name "MANUFACTURER") "KOA Speer") (field (name "PART NUMBER") "RK73Z1ETTP"))
      (libsource (lib "Altium Content Vault") (part "RES"))
    )
    (comp (ref "R80")
      (value "0_5%_0402")
      (footprint "RESC1005X40X25LL10T10")
      (fields (field (name "MANUFACTURER") "KOA Speer") (field (name "PART NUMBER") "RK73Z1ETTP"))
      (libsource (lib "Altium Content Vault") (part "RES"))
    )
    (comp (ref "R81")
      (value "0_5%_0402")
      (footprint "FP-AC0402-0_37-IPC_B")
      (description "RESISTOR 0402 JUMPER ZERO OHM")
      (fields (field (name "TOLERANCE") "1%"))
      (libsource (lib "Altium Content Vault") (part "1029c3af85768c4190bb7ad29bc67b5"))
    )
    (comp (ref "R82")
      (value "4.7K_1%_0402")
      (footprint "RESC1005X40X25NL10T10")
      (fields (field (name "MANUFACTURER") "Bourns") (field (name "PART NUMBER") "CR0402-FX-4701GLF"))
      (libsource (lib "Altium Content Vault") (part "RES"))
    )
    (comp (ref "R83")
      (value "4.7K_1%_0402")
      (footprint "RESC1005X40X25NL10T10")
      (fields (field (name "MANUFACTURER") "Bourns") (field (name "PART NUMBER") "CR0402-FX-4701GLF"))
      (libsource (lib "Altium Content Vault") (part "RES"))
    )
    (comp (ref "R84")
      (value "4.7K_1%_0402")
      (footprint "RESC1005X40X25NL10T10")
      (fields (field (name "MANUFACTURER") "Bourns") (field (name "PART NUMBER") "CR0402-FX-4701GLF"))
      (libsource (lib "Altium Content Vault") (part "RES"))
    )
    (comp (ref "R87")
      (value "100_1%_0402")
      (footprint "RESC1005X40X25ML05T10")
      (fields (field (name "PART NUMBER") "ERJ-U02F1000X") (field (name "MANUFACTURER") "Panasonic"))
      (libsource (lib "Altium Content Vault") (part "RES"))
    )
    (comp (ref "R88")
      (value "49.9_1%_0402")
      (footprint "RESC1005X40X25NL10T10")
      (fields (field (name "PART NUMBER") "RK73H1ETTP49R9F") (field (name "MANUFACTURER") "KOA Speer"))
      (libsource (lib "Altium Content Vault") (part "RES"))
    )
    (comp (ref "R89")
      (value "100_1%_0402")
      (footprint "RESC1005X40X25ML05T10")
      (fields (field (name "PART NUMBER") "ERJ-U02F1000X") (field (name "MANUFACTURER") "Panasonic"))
      (libsource (lib "Altium Content Vault") (part "RES"))
    )
    (comp (ref "Y2")
      (value "SiTime_SiT5501AC-WU-33E0-10T")
      (footprint "SITIME_SPL-086-CQFN-010-C07050_REV_DRAFT")
      (description "OSC, MEMS, STRATUM 3E, 10.000MHZ, 10PPB STAB, LVCMOS, 3.3V, O/P EN, 7.0X5.0X2.2MM, CQFN-10")
      (fields
        (field (name "MANUFACTURER PART NUMBER") "SiT5501AI-WU033JH-10.000000")
        (field (name "MANUFACTURER") "SiTime")
      )
      (libsource (lib "OCXO_DaughterCard") (part "CMP-OSC-00029-2"))
    )
    (comp (ref "Y3")
      (value "ASEMPC-40.000MHZ-XR-T")
      (footprint "FP-ASEMP-CMOS-MFG")
      (description "MEMS Oscillator 40MHz ±25ppm CMOS 2.25V~3.6V 6-SMD 3.2mm x 2.5mm")
      (libsource (lib "Altium Content Vault") (part "9526c112e3a98a1af86e8f4e974a861"))
    )
  )
  (nets
    (net (code "1") (name "DPLL_OSCI") (class "Default")
      (node (ref "C152") (pin "2") (pinfunction "2_2") (pintype "passive"))
    )
    (net (code "2") (name "DPLL_VDDA_BG_LC") (class "Default")
      (node (ref "C83") (pin "1") (pinfunction "1_1") (pintype "passive"))
      (node (ref "C84") (pin "1") (pinfunction "1_1") (pintype "passive"))
      (node (ref "C85") (pin "1") (pinfunction "1_1") (pintype "passive"))
      (node (ref "L2") (pin "2") (pinfunction "2_2") (pintype "passive"))
    )
    (net (code "3") (name "DPLL_VDDA_FB") (class "Default")
      (node (ref "C125") (pin "1") (pinfunction "1_1") (pintype "passive"))
      (node (ref "C126") (pin "1") (pinfunction "1_1") (pintype "passive"))
      (node (ref "L13") (pin "2") (pinfunction "2_2") (pintype "passive"))
    )
    (net (code "4") (name "DPLL_VDDA_PDCP_XTAL") (class "Default")
      (node (ref "C100") (pin "1") (pinfunction "1_1") (pintype "passive"))
      (node (ref "C99") (pin "1") (pinfunction "1_1") (pintype "passive"))
      (node (ref "L5") (pin "2") (pinfunction "2_2") (pintype "passive"))
    )
    (net (code "5") (name "DPLL_VDDO_Q0") (class "Default")
      (node (ref "C111") (pin "1") (pinfunction "1_1") (pintype "passive"))
      (node (ref "C112") (pin "1") (pinfunction "1_1") (pintype "passive"))
      (node (ref "L8") (pin "2") (pinfunction "2_2") (pintype "passive"))
    )
    (net (code "6") (name "DPLL_VDDO_Q1") (class "Default")
      (node (ref "C127") (pin "1") (pinfunction "1_1") (pintype "passive"))
      (node (ref "C128") (pin "1") (pinfunction "1_1") (pintype "passive"))
      (node (ref "L12") (pin "2") (pinfunction "2_2") (pintype "passive"))
    )
    (net (code "7") (name "DPLL_VDDO_Q2") (class "Default")
      (node (ref "C139") (pin "1") (pinfunction "1_1") (pintype "passive"))
      (node (ref "C140") (pin "1") (pinfunction "1_1") (pintype "passive"))
      (node (ref "L16") (pin "2") (pinfunction "2_2") (pintype "passive"))
    )
    (net (code "8") (name "DPLL_VDDO_Q3") (class "Default")
      (node (ref "C148") (pin "1") (pinfunction "1_1") (pintype "passive"))
      (node (ref "C149") (pin "1") (pinfunction "1_1") (pintype "passive"))
      (node (ref "L18") (pin "2") (pinfunction "2_2") (pintype "passive"))
    )
    (net (code "9") (name "DPLL_VDDO_Q4") (class "Default")
      (node (ref "C106") (pin "1") (pinfunction "1_1") (pintype "passive"))
      (node (ref "C107") (pin "1") (pinfunction "1_1") (pintype "passive"))
      (node (ref "L7") (pin "2") (pinfunction "2_2") (pintype "passive"))
    )
    (net (code "10") (name "DPLL_VDDO_Q5") (class "Default")
      (node (ref "C118") (pin "1") (pinfunction "1_1") (pintype "passive"))
      (node (ref "C119") (pin "1") (pinfunction "1_1") (pintype "passive"))
      (node (ref "L10") (pin "2") (pinfunction "2_2") (pintype "passive"))
    )
    (net (code "11") (name "DPLL_VDDO_Q6") (class "Default")
      (node (ref "C132") (pin "1") (pinfunction "1_1") (pintype "passive"))
      (node (ref "C133") (pin "1") (pinfunction "1_1") (pintype "passive"))
      (node (ref "L14") (pin "2") (pinfunction "2_2") (pintype "passive"))
    )
    (net (code "12") (name "DPLL_VDDO_Q7") (class "Default")
      (node (ref "C143") (pin "1") (pinfunction "1_1") (pintype "passive"))
      (node (ref "C144") (pin "1") (pinfunction "1_1") (pintype "passive"))
      (node (ref "L17") (pin "2") (pinfunction "2_2") (pintype "passive"))
    )
    (net (code "13") (name "DPLL_VDD_CLKA") (class "Default")
      (node (ref "C134") (pin "1") (pinfunction "1_1") (pintype "passive"))
      (node (ref "C135") (pin "1") (pinfunction "1_1") (pintype "passive"))
      (node (ref "L15") (pin "2") (pinfunction "2_2") (pintype "passive"))
    )
    (net (code "14") (name "DPLL_VDD_CLKB") (class "Default")
      (node (ref "C120") (pin "1") (pinfunction "1_1") (pintype "passive"))
      (node (ref "C121") (pin "1") (pinfunction "1_1") (pintype "passive"))
      (node (ref "L11") (pin "2") (pinfunction "2_2") (pintype "passive"))
    )
    (net (code "15") (name "DPLL_VDD_DCO_Q0123") (class "Default")
      (node (ref "C102") (pin "1") (pinfunction "1_1") (pintype "passive"))
      (node (ref "C103") (pin "1") (pinfunction "1_1") (pintype "passive"))
      (node (ref "L6") (pin "2") (pinfunction "2_2") (pintype "passive"))
    )
    (net (code "16") (name "DPLL_VDD_DCO_Q4567") (class "Default")
      (node (ref "C113") (pin "1") (pinfunction "1_1") (pintype "passive"))
      (node (ref "C114") (pin "1") (pinfunction "1_1") (pintype "passive"))
      (node (ref "L9") (pin "2") (pinfunction "2_2") (pintype "passive"))
    )
    (net (code "17") (name "DPLL_VDD_DIA_A") (class "Default")
      (node (ref "C77") (pin "1") (pinfunction "1_1") (pintype "passive"))
      (node (ref "C78") (pin "1") (pinfunction "1_1") (pintype "passive"))
      (node (ref "L3") (pin "2") (pinfunction "2_2") (pintype "passive"))
    )
    (net (code "18") (name "DPLL_VDD_DIA_B") (class "Default")
      (node (ref "C92") (pin "1") (pinfunction "1_1") (pintype "passive"))
      (node (ref "C93") (pin "1") (pinfunction "1_1") (pintype "passive"))
      (node (ref "L4") (pin "2") (pinfunction "2_2") (pintype "passive"))
    )
    (net (code "19") (name "DPLL_VDD_DIG") (class "Default")
      (node (ref "C79") (pin "1") (pinfunction "1_1") (pintype "passive"))
      (node (ref "C80") (pin "1") (pinfunction "1_1") (pintype "passive"))
      (node (ref "C81") (pin "1") (pinfunction "1_1") (pintype "passive"))
      (node (ref "C82") (pin "1") (pinfunction "1_1") (pintype "passive"))
      (node (ref "R79") (pin "2") (pinfunction "2_2") (pintype "passive"))
    )
    (net (code "20") (name "DPLL_VDD_GPIO") (class "Default")
      (node (ref "C95") (pin "1") (pinfunction "1_1") (pintype "passive"))
      (node (ref "C96") (pin "1") (pinfunction "1_1") (pintype "passive"))
      (node (ref "C97") (pin "1") (pinfunction "1_1") (pintype "passive"))
      (node (ref "C98") (pin "1") (pinfunction "1_1") (pintype "passive"))
      (node (ref "R80") (pin "2") (pinfunction "2_2") (pintype "passive"))
    )
    (net (code "21") (name "DPLL_XO") (class "Default")
      (node (ref "R81") (pin "1") (pinfunction "1_1") (pintype "passive"))
    )
    (net (code "22") (name "GND") (class "Default")
      (node (ref "C100") (pin "2") (pinfunction "2_2") (pintype "passive"))
      (node (ref "C101") (pin "2") (pinfunction "2_2") (pintype "passive"))
      (node (ref "C102") (pin "2") (pinfunction "2_2") (pintype "passive"))
      (node (ref "C103") (pin "2") (pinfunction "2_2") (pintype "passive"))
      (node (ref "C104") (pin "2") (pinfunction "2_2") (pintype "passive"))
      (node (ref "C105") (pin "2") (pinfunction "2_2") (pintype "passive"))
      (node (ref "C106") (pin "2") (pinfunction "2_2") (pintype "passive"))
      (node (ref "C107") (pin "2") (pinfunction "2_2") (pintype "passive"))
      (node (ref "C108") (pin "2") (pinfunction "2_2") (pintype "passive"))
      (node (ref "C109") (pin "2") (pinfunction "2_2") (pintype "passive"))
      (node (ref "C110") (pin "2") (pinfunction "2_2") (pintype "passive"))
      (node (ref "C111") (pin "2") (pinfunction "2_2") (pintype "passive"))
      (node (ref "C112") (pin "2") (pinfunction "2_2") (pintype "passive"))
      (node (ref "C113") (pin "2") (pinfunction "2_2") (pintype "passive"))
      (node (ref "C114") (pin "2") (pinfunction "2_2") (pintype "passive"))
      (node (ref "C115") (pin "2") (pinfunction "2_2") (pintype "passive"))
      (node (ref "C116") (pin "2") (pinfunction "2_2") (pintype "passive"))
      (node (ref "C117") (pin "2") (pinfunction "2_2") (pintype "passive"))
      (node (ref "C118") (pin "2") (pinfunction "2_2") (pintype "passive"))
      (node (ref "C119") (pin "2") (pinfunction "2_2") (pintype "passive"))
      (node (ref "C120") (pin "2") (pinfunction "2_2") (pintype "passive"))
      (node (ref "C121") (pin "2") (pinfunction "2_2") (pintype "passive"))
      (node (ref "C122") (pin "2") (pinfunction "2_2") (pintype "passive"))
      (node (ref "C123") (pin "2") (pinfunction "2_2") (pintype "passive"))
      (node (ref "C124") (pin "2") (pinfunction "2_2") (pintype "passive"))
      (node (ref "C125") (pin "2") (pinfunction "2_2") (pintype "passive"))
      (node (ref "C126") (pin "2") (pinfunction "2_2") (pintype "passive"))
      (node (ref "C127") (pin "2") (pinfunction "2_2") (pintype "passive"))
      (node (ref "C128") (pin "2") (pinfunction "2_2") (pintype "passive"))
      (node (ref "C129") (pin "2") (pinfunction "2_2") (pintype "passive"))
      (node (ref "C130") (pin "2") (pinfunction "2_2") (pintype "passive"))
      (node (ref "C131") (pin "2") (pinfunction "2_2") (pintype "passive"))
      (node (ref "C132") (pin "2") (pinfunction "2_2") (pintype "passive"))
      (node (ref "C133") (pin "2") (pinfunction "2_2") (pintype "passive"))
      (node (ref "C134") (pin "2") (pinfunction "2_2") (pintype "passive"))
      (node (ref "C135") (pin "2") (pinfunction "2_2") (pintype "passive"))
      (node (ref "C136") (pin "2") (pinfunction "2_2") (pintype "passive"))
      (node (ref "C137") (pin "2") (pinfunction "2_2") (pintype "passive"))
      (node (ref "C138") (pin "2") (pinfunction "2_2") (pintype "passive"))
      (node (ref "C139") (pin "2") (pinfunction "2_2") (pintype "passive"))
      (node (ref "C140") (pin "2") (pinfunction "2_2") (pintype "passive"))
      (node (ref "C141") (pin "2") (pinfunction "2_2") (pintype "passive"))
      (node (ref "C142") (pin "2") (pinfunction "2_2") (pintype "passive"))
      (node (ref "C143") (pin "2") (pinfunction "2_2") (pintype "passive"))
      (node (ref "C144") (pin "2") (pinfunction "2_2") (pintype "passive"))
      (node (ref "C145") (pin "1") (pinfunction "1_1") (pintype "passive"))
      (node (ref "C146") (pin "2") (pinfunction "2_2") (pintype "passive"))
      (node (ref "C147") (pin "2") (pinfunction "2_2") (pintype "passive"))
      (node (ref "C148") (pin "2") (pinfunction "2_2") (pintype "passive"))
      (node (ref "C149") (pin "2") (pinfunction "2_2") (pintype "passive"))
      (node (ref "C150") (pin "2") (pinfunction "2_2") (pintype "passive"))
      (node (ref "C151") (pin "1") (pinfunction "1_1") (pintype "passive"))
      (node (ref "C153") (pin "2") (pinfunction "2_2") (pintype "passive"))
      (node (ref "C154") (pin "2") (pinfunction "2_2") (pintype "passive"))
      (node (ref "C155") (pin "2") (pinfunction "2_2") (pintype "passive"))
      (node (ref "C156") (pin "2") (pinfunction "2_2") (pintype "passive"))
      (node (ref "C77") (pin "2") (pinfunction "2_2") (pintype "passive"))
      (node (ref "C78") (pin "2") (pinfunction "2_2") (pintype "passive"))
      (node (ref "C79") (pin "2") (pinfunction "2_2") (pintype "passive"))
      (node (ref "C80") (pin "2") (pinfunction "2_2") (pintype "passive"))
      (node (ref "C81") (pin "2") (pinfunction "2_2") (pintype "passive"))
      (node (ref "C82") (pin "2") (pinfunction "2_2") (pintype "passive"))
      (node (ref "C83") (pin "2") (pinfunction "2_2") (pintype "passive"))
      (node (ref "C84") (pin "2") (pinfunction "2_2") (pintype "passive"))
      (node (ref "C85") (pin "2") (pinfunction "2_2") (pintype "passive"))
      (node (ref "C86") (pin "2") (pinfunction "2_2") (pintype "passive"))
      (node (ref "C87") (pin "2") (pinfunction "2_2") (pintype "passive"))
      (node (ref "C88") (pin "2") (pinfunction "2_2") (pintype "passive"))
      (node (ref "C89") (pin "2") (pinfunction "2_2") (pintype "passive"))
      (node (ref "C90") (pin "2") (pinfunction "2_2") (pintype "passive"))
      (node (ref "C91") (pin "2") (pinfunction "2_2") (pintype "passive"))
      (node (ref "C92") (pin "2") (pinfunction "2_2") (pintype "passive"))
      (node (ref "C93") (pin "2") (pinfunction "2_2") (pintype "passive"))
      (node (ref "C94") (pin "2") (pinfunction "2_2") (pintype "passive"))
      (node (ref "C95") (pin "2") (pinfunction "2_2") (pintype "passive"))
      (node (ref "C96") (pin "2") (pinfunction "2_2") (pintype "passive"))
      (node (ref "C97") (pin "2") (pinfunction "2_2") (pintype "passive"))
      (node (ref "C98") (pin "2") (pinfunction "2_2") (pintype "passive"))
      (node (ref "C99") (pin "2") (pinfunction "2_2") (pintype "passive"))
      (node (ref "R89") (pin "1") (pinfunction "1_1") (pintype "passive"))
      (node (ref "Y2") (pin "5") (pinfunction "GND_5") (pintype "power_in"))
      (node (ref "Y3") (pin "3") (pinfunction "GND_3") (pintype "power_in"))
    )
    (net (code "23") (name "Net-(C152-Pad1)") (class "Default")
      (node (ref "C152") (pin "1") (pinfunction "1_1") (pintype "passive"))
      (node (ref "R87") (pin "1") (pinfunction "1_1") (pintype "passive"))
      (node (ref "R88") (pin "2") (pinfunction "2_2") (pintype "passive"))
      (node (ref "R89") (pin "2") (pinfunction "2_2") (pintype "passive"))
    )
    (net (code "24") (name "Net-(R83-Pad1)") (class "Default")
      (node (ref "R83") (pin "1") (pinfunction "1_1") (pintype "passive"))
      (node (ref "Y2") (pin "7") (pinfunction "NC_7") (pintype "passive"))
    )
    (net (code "25") (name "Net-(R84-Pad1)") (class "Default")
      (node (ref "R84") (pin "1") (pinfunction "1_1") (pintype "passive"))
      (node (ref "Y2") (pin "8") (pinfunction "NC_8") (pintype "passive"))
    )
    (net (code "26") (name "Net-(Y2-CLK)") (class "Default")
      (node (ref "R81") (pin "2") (pinfunction "2_2") (pintype "passive"))
      (node (ref "Y2") (pin "6") (pinfunction "CLK_6") (pintype "output"))
    )
    (net (code "27") (name "Net-(Y2-OE)") (class "Default")
      (node (ref "R82") (pin "2") (pinfunction "2_2") (pintype "passive"))
      (node (ref "Y2") (pin "1") (pinfunction "OE_1") (pintype "input"))
    )
    (net (code "28") (name "Net-(Y2-VDD)") (class "Default")
      (node (ref "C150") (pin "1") (pinfunction "1_1") (pintype "passive"))
      (node (ref "C151") (pin "2") (pinfunction "2_2") (pintype "passive"))
      (node (ref "FB5") (pin "1") (pinfunction "1_1") (pintype "passive"))
      (node (ref "R82") (pin "1") (pinfunction "1_1") (pintype "passive"))
      (node (ref "Y2") (pin "10") (pinfunction "VDD_10") (pintype "power_in"))
    )
    (net (code "29") (name "Net-(Y3-Output)") (class "Default")
      (node (ref "R88") (pin "1") (pinfunction "1_1") (pintype "passive"))
      (node (ref "Y3") (pin "4") (pinfunction "Output_4") (pintype "output"))
    )
    (net (code "30") (name "Net-(Y3-VDD)") (class "Default")
      (node (ref "C155") (pin "1") (pinfunction "1_1") (pintype "passive"))
      (node (ref "C156") (pin "1") (pinfunction "1_1") (pintype "passive"))
      (node (ref "L19") (pin "2") (pinfunction "2_2") (pintype "passive"))
      (node (ref "Y3") (pin "1") (pinfunction "~{Tri-State}_1") (pintype "input"))
      (node (ref "Y3") (pin "6") (pinfunction "VDD_6") (pintype "power_in"))
    )
    (net (code "31") (name "P1V8") (class "Default")
      (node (ref "C108") (pin "1") (pinfunction "1_1") (pintype "passive"))
      (node (ref "C115") (pin "1") (pinfunction "1_1") (pintype "passive"))
      (node (ref "C129") (pin "1") (pinfunction "1_1") (pintype "passive"))
      (node (ref "C88") (pin "1") (pinfunction "1_1") (pintype "passive"))
      (node (ref "C89") (pin "1") (pinfunction "1_1") (pintype "passive"))
      (node (ref "C90") (pin "1") (pinfunction "1_1") (pintype "passive"))
      (node (ref "C94") (pin "1") (pinfunction "1_1") (pintype "passive"))
      (node (ref "L13") (pin "1") (pinfunction "1_1") (pintype "passive"))
      (node (ref "L3") (pin "1") (pinfunction "1_1") (pintype "passive"))
      (node (ref "L4") (pin "1") (pinfunction "1_1") (pintype "passive"))
      (node (ref "L6") (pin "1") (pinfunction "1_1") (pintype "passive"))
      (node (ref "L9") (pin "1") (pinfunction "1_1") (pintype "passive"))
      (node (ref "R79") (pin "1") (pinfunction "1_1") (pintype "passive"))
    )
    (net (code "32") (name "P3V3") (class "Default")
      (node (ref "C101") (pin "1") (pinfunction "1_1") (pintype "passive"))
      (node (ref "C104") (pin "1") (pinfunction "1_1") (pintype "passive"))
      (node (ref "C105") (pin "1") (pinfunction "1_1") (pintype "passive"))
      (node (ref "C109") (pin "1") (pinfunction "1_1") (pintype "passive"))
      (node (ref "C110") (pin "1") (pinfunction "1_1") (pintype "passive"))
      (node (ref "C116") (pin "1") (pinfunction "1_1") (pintype "passive"))
      (node (ref "C117") (pin "1") (pinfunction "1_1") (pintype "passive"))
      (node (ref "C122") (pin "1") (pinfunction "1_1") (pintype "passive"))
      (node (ref "C123") (pin "1") (pinfunction "1_1") (pintype "passive"))
      (node (ref "C124") (pin "1") (pinfunction "1_1") (pintype "passive"))
      (node (ref "C130") (pin "1") (pinfunction "1_1") (pintype "passive"))
      (node (ref "C131") (pin "1") (pinfunction "1_1") (pintype "passive"))
      (node (ref "C136") (pin "1") (pinfunction "1_1") (pintype "passive"))
      (node (ref "C137") (pin "1") (pinfunction "1_1") (pintype "passive"))
      (node (ref "C138") (pin "1") (pinfunction "1_1") (pintype "passive"))
      (node (ref "C141") (pin "1") (pinfunction "1_1") (pintype "passive"))
      (node (ref "C142") (pin "1") (pinfunction "1_1") (pintype "passive"))
      (node (ref "C145") (pin "2") (pinfunction "2_2") (pintype "passive"))
      (node (ref "C146") (pin "1") (pinfunction "1_1") (pintype "passive"))
      (node (ref "C147") (pin "1") (pinfunction "1_1") (pintype "passive"))
      (node (ref "C153") (pin "1") (pinfunction "1_1") (pintype "passive"))
      (node (ref "C154") (pin "1") (pinfunction "1_1") (pintype "passive"))
      (node (ref "C86") (pin "1") (pinfunction "1_1") (pintype "passive"))
      (node (ref "C87") (pin "1") (pinfunction "1_1") (pintype "passive"))
      (node (ref "C91") (pin "1") (pinfunction "1_1") (pintype "passive"))
      (node (ref "FB5") (pin "2") (pinfunction "2_2") (pintype "passive"))
      (node (ref "L10") (pin "1") (pinfunction "1_1") (pintype "passive"))
      (node (ref "L11") (pin "1") (pinfunction "1_1") (pintype "passive"))
      (node (ref "L12") (pin "1") (pinfunction "1_1") (pintype "passive"))
      (node (ref "L14") (pin "1") (pinfunction "1_1") (pintype "passive"))
      (node (ref "L15") (pin "1") (pinfunction "1_1") (pintype "passive"))
      (node (ref "L16") (pin "1") (pinfunction "1_1") (pintype "passive"))
      (node (ref "L17") (pin "1") (pinfunction "1_1") (pintype "passive"))
      (node (ref "L18") (pin "1") (pinfunction "1_1") (pintype "passive"))
      (node (ref "L19") (pin "1") (pinfunction "1_1") (pintype "passive"))
      (node (ref "L2") (pin "1") (pinfunction "1_1") (pintype "passive"))
      (node (ref "L5") (pin "1") (pinfunction "1_1") (pintype "passive"))
      (node (ref "L7") (pin "1") (pinfunction "1_1") (pintype "passive"))
      (node (ref "L8") (pin "1") (pinfunction "1_1") (pintype "passive"))
      (node (ref "R80") (pin "1") (pinfunction "1_1") (pintype "passive"))
      (node (ref "R83") (pin "2") (pinfunction "2_2") (pintype "passive"))
      (node (ref "R84") (pin "2") (pinfunction "2_2") (pintype "passive"))
      (node (ref "R87") (pin "2") (pinfunction "2_2") (pintype "passive"))
    )
    (net (code "33") (name "TOP_SENS_I2C_SCL") (class "Default")
      (node (ref "Y2") (pin "3") (pinfunction "NC_3") (pintype "passive"))
    )
    (net (code "34") (name "TOP_SENS_I2C_SDA") (class "Default")
      (node (ref "Y2") (pin "2") (pinfunction "NC_2") (pintype "passive"))
    )
    (net (code "35") (name "unconnected-(Y2-NC-Pad4)") (class "Default")
      (node (ref "Y2") (pin "4") (pinfunction "NC_4") (pintype "passive"))
    )
    (net (code "36") (name "unconnected-(Y2-NC-Pad9)") (class "Default")
      (node (ref "Y2") (pin "9") (pinfunction "NC_9") (pintype "passive"))
    )
  )
)
